# PROJECT.net
KiCad netlist of a schematic drawn in EasyEDA Pro
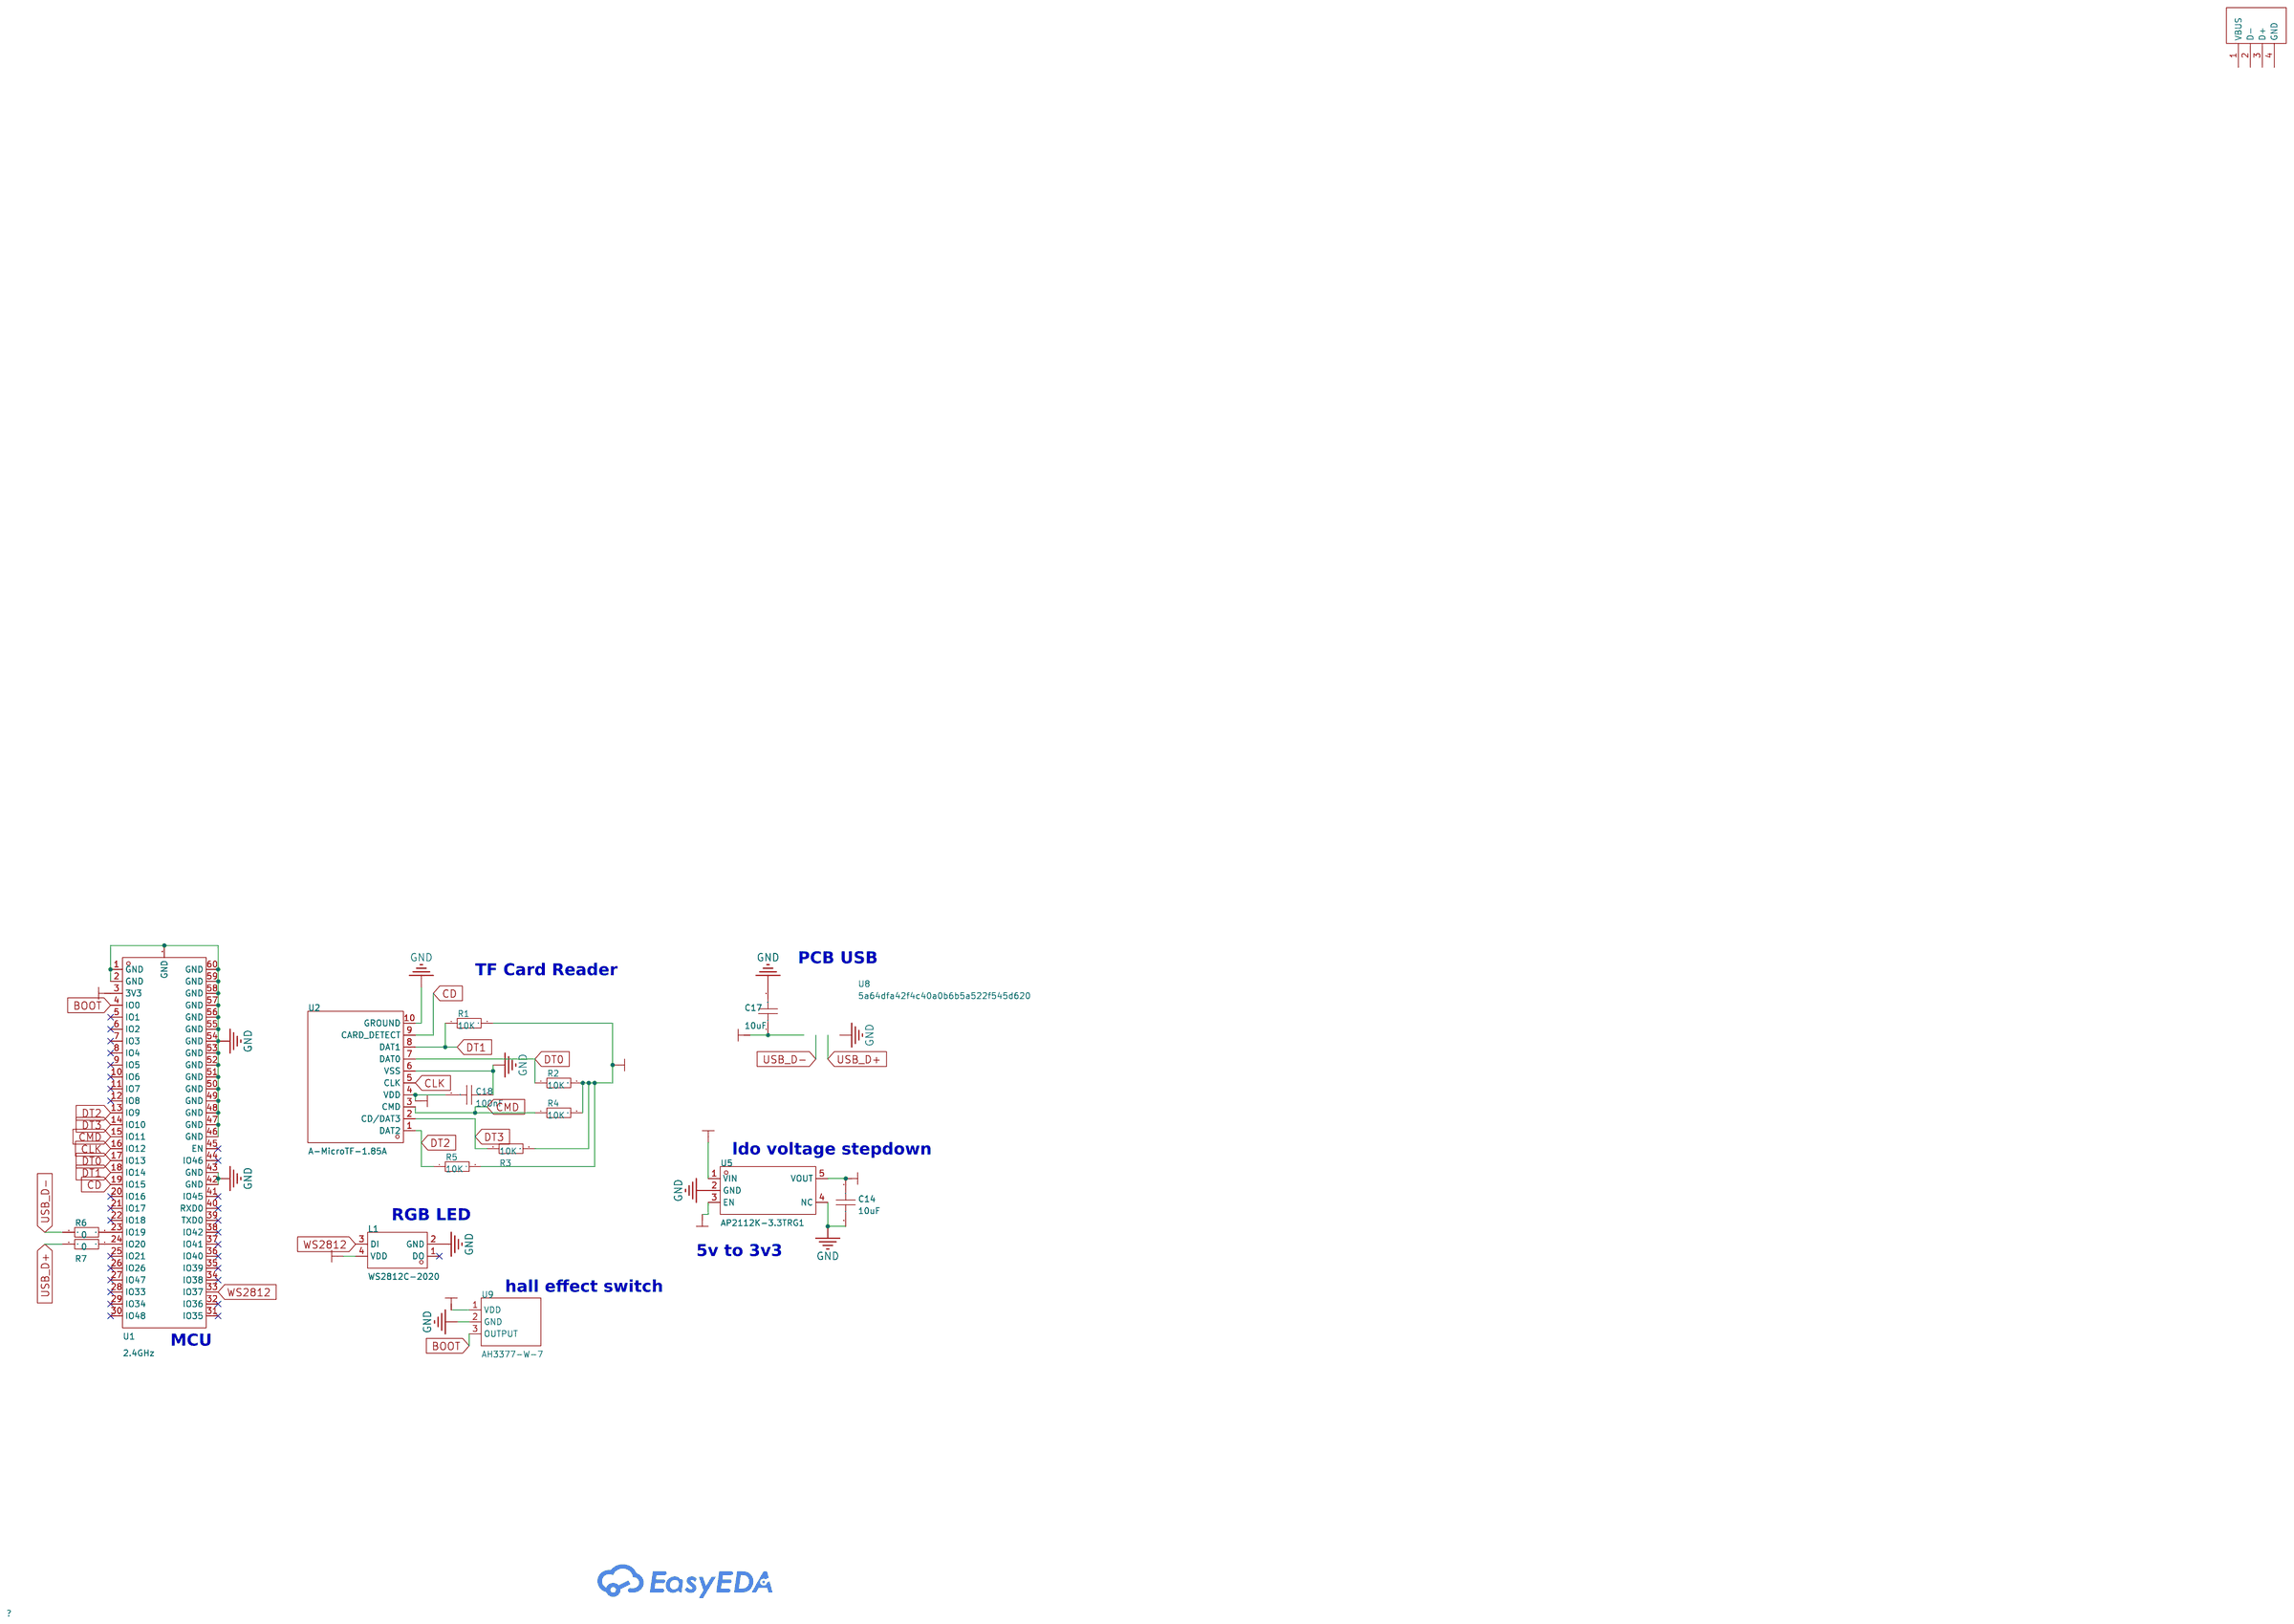
[diagram p0: schematic sheet]

(export (version "E")
  (design (tool "Eeschema 10.0.6"))
  (components
    (comp (ref "C14")
      (value "10uF")
      (footprint "easyedapro:C0603")
      (libsource (lib "easyedapro") (part "CAP"))
    )
    (comp (ref "C17")
      (value "10uF")
      (footprint "easyedapro:C0603")
      (libsource (lib "easyedapro") (part "CAP"))
    )
    (comp (ref "C18")
      (value "100nF")
      (footprint "easyedapro:C0603")
      (libsource (lib "easyedapro") (part "CAP"))
    )
    (comp (ref "L1")
      (value "WS2812C-2020")
      (footprint "easyedapro:LED-SMD_L2.2-W2.0")
      (description "Wavelength:460nm；520nm；623nm Operating Temperature:-25°C~+85°C")
      (fields (field (name "Manufacturer") "worldsemi"))
      (libsource (lib "easyedapro") (part "WS2812C-2020"))
    )
    (comp (ref "R1") (value "10K") (footprint "easyedapro:R0603") (libsource (lib "easyedapro") (part "Res")))
    (comp (ref "R2") (value "10K") (footprint "easyedapro:R0603") (libsource (lib "easyedapro") (part "Res")))
    (comp (ref "R3") (value "10K") (footprint "easyedapro:R0603") (libsource (lib "easyedapro") (part "Res")))
    (comp (ref "R4") (value "10K") (footprint "easyedapro:R0603") (libsource (lib "easyedapro") (part "Res")))
    (comp (ref "R5") (value "10K") (footprint "easyedapro:R0603") (libsource (lib "easyedapro") (part "Res")))
    (comp (ref "R6") (value "0") (footprint "easyedapro:R0603") (libsource (lib "easyedapro") (part "Res")))
    (comp (ref "R7") (value "0") (footprint "easyedapro:R0603") (libsource (lib "easyedapro") (part "Res")))
    (comp (ref "U1")
      (value "2.4GHz")
      (footprint "easyedapro:BULETM-SMD_ESP32-S3-MINI-1-N8")
      (fields
        (field (name "Manufacturer Part") "ESP32-S3-MINI-1-N8")
        (field (name "Manufacturer") "ESPRESSIF(乐鑫)")
      )
      (libsource (lib "easyedapro") (part "ESP32-S3-MINI-1-N8"))
    )
    (comp (ref "U2")
      (value "A-MicroTF-1.85A")
      (footprint "easyedapro:TF-SMD_A-MICROTF-1.85A")
      (fields (field (name "Manufacturer") "MyAntenna(摩天射频)"))
      (libsource (lib "easyedapro") (part "A-MICROTF-1.85A"))
    )
    (comp (ref "U5")
      (value "AP2112K-3.3TRG1")
      (footprint "easyedapro:SOT-25-5_L2.9-W1.6-P0.95-LS2.8-BL")
      (fields (field (name "Manufacturer") "DIODES(美台)"))
      (libsource (lib "easyedapro") (part "AP2112K-3.3TRG1"))
    )
    (comp (ref "U8")
      (value "5a64dfa42f4c40a0b6b5a522f545d620")
      (footprint "easyedapro:USB-A_PCB")
      (libsource (lib "easyedapro") (part "USB-A_PCB"))
    )
    (comp (ref "U9")
      (value "AH3377-W-7")
      (footprint "easyedapro:SC-59-3_L3.0-W1.6-P0.95-LS2.9-BR-CW")
      (fields (field (name "Manufacturer") "DIODES(美台)"))
      (libsource (lib "easyedapro") (part "AH3377-W-7"))
    )
  )
  (nets
    (net (code "1") (name "+3V3") (class "Default")
      (node (ref "C14") (pin "1") (pinfunction "1_1") (pintype "input"))
      (node (ref "C18") (pin "2") (pinfunction "2_2") (pintype "input"))
      (node (ref "L1") (pin "4") (pinfunction "VDD_4") (pintype "unspecified"))
      (node (ref "R1") (pin "2") (pinfunction "2_2") (pintype "input"))
      (node (ref "R2") (pin "2") (pinfunction "2_2") (pintype "input"))
      (node (ref "R3") (pin "2") (pinfunction "2_2") (pintype "input"))
      (node (ref "R4") (pin "2") (pinfunction "2_2") (pintype "input"))
      (node (ref "R5") (pin "2") (pinfunction "2_2") (pintype "input"))
      (node (ref "U1") (pin "3") (pinfunction "3V3_3") (pintype "unspecified"))
      (node (ref "U2") (pin "4") (pinfunction "VDD_4") (pintype "unspecified"))
      (node (ref "U5") (pin "5") (pinfunction "VOUT_5") (pintype "unspecified"))
      (node (ref "U9") (pin "1") (pinfunction "VDD_1") (pintype "unspecified"))
    )
    (net (code "2") (name "BOOT") (class "Default")
      (node (ref "U1") (pin "4") (pinfunction "IO0_4") (pintype "unspecified"))
      (node (ref "U9") (pin "3") (pinfunction "OUTPUT_3") (pintype "unspecified"))
    )
    (net (code "3") (name "CD") (class "Default")
      (node (ref "U1") (pin "19") (pinfunction "IO15_19") (pintype "unspecified"))
      (node (ref "U2") (pin "9") (pinfunction "CARD_DETECT_9") (pintype "unspecified"))
    )
    (net (code "4") (name "CLK") (class "Default")
      (node (ref "U1") (pin "16") (pinfunction "IO12_16") (pintype "unspecified"))
      (node (ref "U2") (pin "5") (pinfunction "CLK_5") (pintype "unspecified"))
    )
    (net (code "5") (name "CMD") (class "Default")
      (node (ref "R4") (pin "1") (pinfunction "1_1") (pintype "input"))
      (node (ref "U1") (pin "15") (pinfunction "IO11_15") (pintype "unspecified"))
      (node (ref "U2") (pin "3") (pinfunction "CMD_3") (pintype "unspecified"))
    )
    (net (code "6") (name "DT0") (class "Default")
      (node (ref "R2") (pin "1") (pinfunction "1_1") (pintype "input"))
      (node (ref "U1") (pin "17") (pinfunction "IO13_17") (pintype "unspecified"))
      (node (ref "U2") (pin "7") (pinfunction "DAT0_7") (pintype "unspecified"))
    )
    (net (code "7") (name "DT1") (class "Default")
      (node (ref "R1") (pin "1") (pinfunction "1_1") (pintype "input"))
      (node (ref "U1") (pin "18") (pinfunction "IO14_18") (pintype "unspecified"))
      (node (ref "U2") (pin "8") (pinfunction "DAT1_8") (pintype "unspecified"))
    )
    (net (code "8") (name "DT2") (class "Default")
      (node (ref "R5") (pin "1") (pinfunction "1_1") (pintype "input"))
      (node (ref "U1") (pin "13") (pinfunction "IO9_13") (pintype "unspecified"))
      (node (ref "U2") (pin "1") (pinfunction "DAT2_1") (pintype "unspecified"))
    )
    (net (code "9") (name "DT3") (class "Default")
      (node (ref "R3") (pin "1") (pinfunction "1_1") (pintype "input"))
      (node (ref "U1") (pin "14") (pinfunction "IO10_14") (pintype "unspecified"))
      (node (ref "U2") (pin "2") (pinfunction "CD/DAT3_2") (pintype "unspecified"))
    )
    (net (code "10") (name "GND") (class "Default")
      (node (ref "C14") (pin "2") (pinfunction "2_2") (pintype "input"))
      (node (ref "C17") (pin "2") (pinfunction "2_2") (pintype "input"))
      (node (ref "C18") (pin "1") (pinfunction "1_1") (pintype "input"))
      (node (ref "L1") (pin "2") (pinfunction "GND_2") (pintype "unspecified"))
      (node (ref "U1") (pin "1") (pinfunction "GND_1") (pintype "unspecified"))
      (node (ref "U1") (pin "2") (pinfunction "GND_2") (pintype "unspecified"))
      (node (ref "U1") (pin "42") (pinfunction "GND_42") (pintype "unspecified"))
      (node (ref "U1") (pin "43") (pinfunction "GND_43") (pintype "unspecified"))
      (node (ref "U1") (pin "46") (pinfunction "GND_46") (pintype "unspecified"))
      (node (ref "U1") (pin "47") (pinfunction "GND_47") (pintype "unspecified"))
      (node (ref "U1") (pin "48") (pinfunction "GND_48") (pintype "unspecified"))
      (node (ref "U1") (pin "49") (pinfunction "GND_49") (pintype "unspecified"))
      (node (ref "U1") (pin "50") (pinfunction "GND_50") (pintype "unspecified"))
      (node (ref "U1") (pin "51") (pinfunction "GND_51") (pintype "unspecified"))
      (node (ref "U1") (pin "52") (pinfunction "GND_52") (pintype "unspecified"))
      (node (ref "U1") (pin "53") (pinfunction "GND_53") (pintype "unspecified"))
      (node (ref "U1") (pin "54") (pinfunction "GND_54") (pintype "unspecified"))
      (node (ref "U1") (pin "55") (pinfunction "GND_55") (pintype "unspecified"))
      (node (ref "U1") (pin "56") (pinfunction "GND_56") (pintype "unspecified"))
      (node (ref "U1") (pin "57") (pinfunction "GND_57") (pintype "unspecified"))
      (node (ref "U1") (pin "58") (pinfunction "GND_58") (pintype "unspecified"))
      (node (ref "U1") (pin "59") (pinfunction "GND_59") (pintype "unspecified"))
      (node (ref "U1") (pin "60") (pinfunction "GND_60") (pintype "unspecified"))
      (node (ref "U1") (pin "GND") (pinfunction "GND_GND") (pintype "unspecified"))
      (node (ref "U2") (pin "10") (pinfunction "GROUND_10") (pintype "unspecified"))
      (node (ref "U2") (pin "6") (pinfunction "VSS_6") (pintype "unspecified"))
      (node (ref "U5") (pin "2") (pinfunction "GND_2") (pintype "unspecified"))
      (node (ref "U5") (pin "4") (pinfunction "NC_4") (pintype "unspecified"))
      (node (ref "U9") (pin "2") (pinfunction "GND_2") (pintype "unspecified"))
    )
    (net (code "11") (name "Net-(U1-IO19)") (class "Default")
      (node (ref "R6") (pin "2") (pinfunction "2_2") (pintype "input"))
      (node (ref "U1") (pin "23") (pinfunction "IO19_23") (pintype "unspecified"))
    )
    (net (code "12") (name "Net-(U1-IO20)") (class "Default")
      (node (ref "R7") (pin "2") (pinfunction "2_2") (pintype "input"))
      (node (ref "U1") (pin "24") (pinfunction "IO20_24") (pintype "unspecified"))
    )
    (net (code "13") (name "USB_D+") (class "Default")
      (node (ref "R7") (pin "1") (pinfunction "1_1") (pintype "input"))
    )
    (net (code "14") (name "USB_D-") (class "Default")
      (node (ref "R6") (pin "1") (pinfunction "1_1") (pintype "input"))
    )
    (net (code "15") (name "VBUS") (class "Default")
      (node (ref "C17") (pin "1") (pinfunction "1_1") (pintype "input"))
      (node (ref "U5") (pin "1") (pinfunction "VIN_1") (pintype "unspecified"))
      (node (ref "U5") (pin "3") (pinfunction "EN_3") (pintype "unspecified"))
    )
    (net (code "16") (name "WS2812") (class "Default")
      (node (ref "L1") (pin "3") (pinfunction "DI_3") (pintype "unspecified"))
      (node (ref "U1") (pin "33") (pinfunction "IO37_33") (pintype "unspecified"))
    )
    (net (code "17") (name "unconnected-(L1-DO-Pad1)") (class "Default")
      (node (ref "L1") (pin "1") (pinfunction "DO_1") (pintype "unspecified+no_connect"))
    )
    (net (code "18") (name "unconnected-(U1-EN-Pad45)") (class "Default")
      (node (ref "U1") (pin "45") (pinfunction "EN_45") (pintype "unspecified+no_connect"))
    )
    (net (code "19") (name "unconnected-(U1-IO1-Pad5)") (class "Default")
      (node (ref "U1") (pin "5") (pinfunction "IO1_5") (pintype "unspecified+no_connect"))
    )
    (net (code "20") (name "unconnected-(U1-IO2-Pad6)") (class "Default")
      (node (ref "U1") (pin "6") (pinfunction "IO2_6") (pintype "unspecified+no_connect"))
    )
    (net (code "21") (name "unconnected-(U1-IO3-Pad7)") (class "Default")
      (node (ref "U1") (pin "7") (pinfunction "IO3_7") (pintype "unspecified+no_connect"))
    )
    (net (code "22") (name "unconnected-(U1-IO4-Pad8)") (class "Default")
      (node (ref "U1") (pin "8") (pinfunction "IO4_8") (pintype "unspecified+no_connect"))
    )
    (net (code "23") (name "unconnected-(U1-IO5-Pad9)") (class "Default")
      (node (ref "U1") (pin "9") (pinfunction "IO5_9") (pintype "unspecified+no_connect"))
    )
    (net (code "24") (name "unconnected-(U1-IO6-Pad10)") (class "Default")
      (node (ref "U1") (pin "10") (pinfunction "IO6_10") (pintype "unspecified+no_connect"))
    )
    (net (code "25") (name "unconnected-(U1-IO7-Pad11)") (class "Default")
      (node (ref "U1") (pin "11") (pinfunction "IO7_11") (pintype "unspecified+no_connect"))
    )
    (net (code "26") (name "unconnected-(U1-IO8-Pad12)") (class "Default")
      (node (ref "U1") (pin "12") (pinfunction "IO8_12") (pintype "unspecified+no_connect"))
    )
    (net (code "27") (name "unconnected-(U1-IO16-Pad20)") (class "Default")
      (node (ref "U1") (pin "20") (pinfunction "IO16_20") (pintype "unspecified+no_connect"))
    )
    (net (code "28") (name "unconnected-(U1-IO17-Pad21)") (class "Default")
      (node (ref "U1") (pin "21") (pinfunction "IO17_21") (pintype "unspecified+no_connect"))
    )
    (net (code "29") (name "unconnected-(U1-IO18-Pad22)") (class "Default")
      (node (ref "U1") (pin "22") (pinfunction "IO18_22") (pintype "unspecified+no_connect"))
    )
    (net (code "30") (name "unconnected-(U1-IO21-Pad25)") (class "Default")
      (node (ref "U1") (pin "25") (pinfunction "IO21_25") (pintype "unspecified+no_connect"))
    )
    (net (code "31") (name "unconnected-(U1-IO26-Pad26)") (class "Default")
      (node (ref "U1") (pin "26") (pinfunction "IO26_26") (pintype "unspecified+no_connect"))
    )
    (net (code "32") (name "unconnected-(U1-IO33-Pad28)") (class "Default")
      (node (ref "U1") (pin "28") (pinfunction "IO33_28") (pintype "unspecified+no_connect"))
    )
    (net (code "33") (name "unconnected-(U1-IO34-Pad29)") (class "Default")
      (node (ref "U1") (pin "29") (pinfunction "IO34_29") (pintype "unspecified+no_connect"))
    )
    (net (code "34") (name "unconnected-(U1-IO35-Pad31)") (class "Default")
      (node (ref "U1") (pin "31") (pinfunction "IO35_31") (pintype "unspecified+no_connect"))
    )
    (net (code "35") (name "unconnected-(U1-IO36-Pad32)") (class "Default")
      (node (ref "U1") (pin "32") (pinfunction "IO36_32") (pintype "unspecified+no_connect"))
    )
    (net (code "36") (name "unconnected-(U1-IO38-Pad34)") (class "Default")
      (node (ref "U1") (pin "34") (pinfunction "IO38_34") (pintype "unspecified+no_connect"))
    )
    (net (code "37") (name "unconnected-(U1-IO39-Pad35)") (class "Default")
      (node (ref "U1") (pin "35") (pinfunction "IO39_35") (pintype "unspecified+no_connect"))
    )
    (net (code "38") (name "unconnected-(U1-IO40-Pad36)") (class "Default")
      (node (ref "U1") (pin "36") (pinfunction "IO40_36") (pintype "unspecified+no_connect"))
    )
    (net (code "39") (name "unconnected-(U1-IO41-Pad37)") (class "Default")
      (node (ref "U1") (pin "37") (pinfunction "IO41_37") (pintype "unspecified+no_connect"))
    )
    (net (code "40") (name "unconnected-(U1-IO42-Pad38)") (class "Default")
      (node (ref "U1") (pin "38") (pinfunction "IO42_38") (pintype "unspecified+no_connect"))
    )
    (net (code "41") (name "unconnected-(U1-IO45-Pad41)") (class "Default")
      (node (ref "U1") (pin "41") (pinfunction "IO45_41") (pintype "unspecified+no_connect"))
    )
    (net (code "42") (name "unconnected-(U1-IO46-Pad44)") (class "Default")
      (node (ref "U1") (pin "44") (pinfunction "IO46_44") (pintype "unspecified+no_connect"))
    )
    (net (code "43") (name "unconnected-(U1-IO47-Pad27)") (class "Default")
      (node (ref "U1") (pin "27") (pinfunction "IO47_27") (pintype "unspecified+no_connect"))
    )
    (net (code "44") (name "unconnected-(U1-IO48-Pad30)") (class "Default")
      (node (ref "U1") (pin "30") (pinfunction "IO48_30") (pintype "unspecified+no_connect"))
    )
    (net (code "45") (name "unconnected-(U1-RXD0-Pad40)") (class "Default")
      (node (ref "U1") (pin "40") (pinfunction "RXD0_40") (pintype "unspecified+no_connect"))
    )
    (net (code "46") (name "unconnected-(U1-TXD0-Pad39)") (class "Default")
      (node (ref "U1") (pin "39") (pinfunction "TXD0_39") (pintype "unspecified+no_connect"))
    )
    (net (code "47") (name "unconnected-(U8-D+-Pad3)") (class "Default")
      (node (ref "U8") (pin "3") (pinfunction "D+_3") (pintype "input"))
    )
    (net (code "48") (name "unconnected-(U8-D--Pad2)") (class "Default")
      (node (ref "U8") (pin "2") (pinfunction "D-_2") (pintype "input"))
    )
    (net (code "49") (name "unconnected-(U8-GND-Pad4)") (class "Default")
      (node (ref "U8") (pin "4") (pinfunction "GND_4") (pintype "input"))
    )
    (net (code "50") (name "unconnected-(U8-VBUS-Pad1)") (class "Default")
      (node (ref "U8") (pin "1") (pinfunction "VBUS_1") (pintype "input"))
    )
  )
)
